# FLEX_DCDC.net
KiCad netlist of a schematic drawn in EAGLE
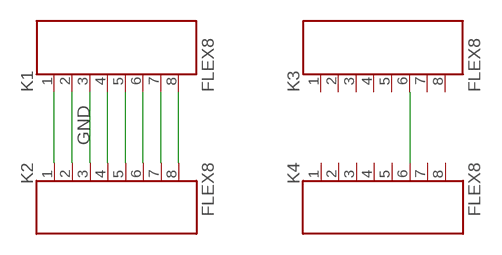
[diagram p0: schematic, sheet 1]

(export (version "E")
  (design (tool "Eeschema 10.0.6"))
  (components
    (comp (ref "K1")
      (value "FLEX8")
      (footprint "eagle-import:FLEX8")
      (libsource (lib "eagle-import") (part "FLEX8"))
    )
    (comp (ref "K2")
      (value "FLEX8")
      (footprint "eagle-import:FLEX8")
      (libsource (lib "eagle-import") (part "FLEX8"))
    )
    (comp (ref "K3")
      (value "FLEX8")
      (footprint "eagle-import:FLEX8")
      (libsource (lib "eagle-import") (part "FLEX8"))
    )
    (comp (ref "K4")
      (value "FLEX8")
      (footprint "eagle-import:FLEX8")
      (libsource (lib "eagle-import") (part "FLEX8"))
    )
  )
  (nets
    (net (code "1") (name "/GND") (class "Default")
      (node (ref "K1") (pin "3") (pinfunction "3_3") (pintype "passive"))
      (node (ref "K2") (pin "3") (pinfunction "3_3") (pintype "passive"))
      (node (ref "K3") (pin "6") (pinfunction "6_6") (pintype "passive"))
      (node (ref "K4") (pin "6") (pinfunction "6_6") (pintype "passive"))
    )
    (net (code "2") (name "Net-(K1-Pad1)") (class "Default")
      (node (ref "K1") (pin "1") (pinfunction "1_1") (pintype "passive"))
      (node (ref "K2") (pin "1") (pinfunction "1_1") (pintype "passive"))
    )
    (net (code "3") (name "Net-(K1-Pad2)") (class "Default")
      (node (ref "K1") (pin "2") (pinfunction "2_2") (pintype "passive"))
      (node (ref "K2") (pin "2") (pinfunction "2_2") (pintype "passive"))
    )
    (net (code "4") (name "Net-(K1-Pad4)") (class "Default")
      (node (ref "K1") (pin "4") (pinfunction "4_4") (pintype "passive"))
      (node (ref "K2") (pin "4") (pinfunction "4_4") (pintype "passive"))
    )
    (net (code "5") (name "Net-(K1-Pad5)") (class "Default")
      (node (ref "K1") (pin "5") (pinfunction "5_5") (pintype "passive"))
      (node (ref "K2") (pin "5") (pinfunction "5_5") (pintype "passive"))
    )
    (net (code "6") (name "Net-(K1-Pad6)") (class "Default")
      (node (ref "K1") (pin "6") (pinfunction "6_6") (pintype "passive"))
      (node (ref "K2") (pin "6") (pinfunction "6_6") (pintype "passive"))
    )
    (net (code "7") (name "Net-(K1-Pad7)") (class "Default")
      (node (ref "K1") (pin "7") (pinfunction "7_7") (pintype "passive"))
      (node (ref "K2") (pin "7") (pinfunction "7_7") (pintype "passive"))
    )
    (net (code "8") (name "Net-(K1-Pad8)") (class "Default")
      (node (ref "K1") (pin "8") (pinfunction "8_8") (pintype "passive"))
      (node (ref "K2") (pin "8") (pinfunction "8_8") (pintype "passive"))
    )
    (net (code "9") (name "unconnected-(K3-Pad1)") (class "Default")
      (node (ref "K3") (pin "1") (pinfunction "1_1") (pintype "passive"))
    )
    (net (code "10") (name "unconnected-(K3-Pad2)") (class "Default")
      (node (ref "K3") (pin "2") (pinfunction "2_2") (pintype "passive"))
    )
    (net (code "11") (name "unconnected-(K3-Pad3)") (class "Default")
      (node (ref "K3") (pin "3") (pinfunction "3_3") (pintype "passive"))
    )
    (net (code "12") (name "unconnected-(K3-Pad4)") (class "Default")
      (node (ref "K3") (pin "4") (pinfunction "4_4") (pintype "passive"))
    )
    (net (code "13") (name "unconnected-(K3-Pad5)") (class "Default")
      (node (ref "K3") (pin "5") (pinfunction "5_5") (pintype "passive"))
    )
    (net (code "14") (name "unconnected-(K3-Pad7)") (class "Default")
      (node (ref "K3") (pin "7") (pinfunction "7_7") (pintype "passive"))
    )
    (net (code "15") (name "unconnected-(K3-Pad8)") (class "Default")
      (node (ref "K3") (pin "8") (pinfunction "8_8") (pintype "passive"))
    )
    (net (code "16") (name "unconnected-(K4-Pad1)") (class "Default")
      (node (ref "K4") (pin "1") (pinfunction "1_1") (pintype "passive"))
    )
    (net (code "17") (name "unconnected-(K4-Pad2)") (class "Default")
      (node (ref "K4") (pin "2") (pinfunction "2_2") (pintype "passive"))
    )
    (net (code "18") (name "unconnected-(K4-Pad3)") (class "Default")
      (node (ref "K4") (pin "3") (pinfunction "3_3") (pintype "passive"))
    )
    (net (code "19") (name "unconnected-(K4-Pad4)") (class "Default")
      (node (ref "K4") (pin "4") (pinfunction "4_4") (pintype "passive"))
    )
    (net (code "20") (name "unconnected-(K4-Pad5)") (class "Default")
      (node (ref "K4") (pin "5") (pinfunction "5_5") (pintype "passive"))
    )
    (net (code "21") (name "unconnected-(K4-Pad7)") (class "Default")
      (node (ref "K4") (pin "7") (pinfunction "7_7") (pintype "passive"))
    )
    (net (code "22") (name "unconnected-(K4-Pad8)") (class "Default")
      (node (ref "K4") (pin "8") (pinfunction "8_8") (pintype "passive"))
    )
  )
)
